# modular_pcb2.net
KiCad netlist of a schematic drawn in EAGLE
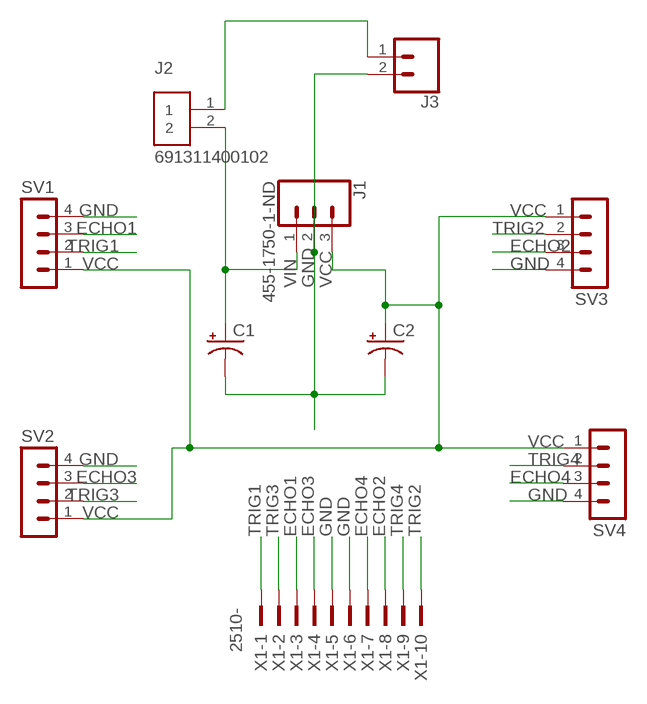
[diagram p0: schematic, sheet 1]

(export (version "E")
  (design (tool "Eeschema 10.0.6"))
  (components
    (comp (ref "C1")
      (value "1F-2.7V(PTH)CPOL-RADIAL-1H-2.7V")
      (footprint "eagle-import:CPOL-RADIAL-1F-2.7V")
      (libsource (lib "eagle-import") (part "1F-2.7V(PTH)CPOL-RADIAL-1H-2.7V"))
    )
    (comp (ref "C2")
      (value "1F-2.7V(PTH)CPOL-RADIAL-1H-2.7V")
      (footprint "eagle-import:CPOL-RADIAL-1F-2.7V")
      (libsource (lib "eagle-import") (part "1F-2.7V(PTH)CPOL-RADIAL-1H-2.7V"))
    )
    (comp (ref "J1")
      (value "455-1750-1-ND")
      (footprint "eagle-import:1X03")
      (libsource (lib "eagle-import") (part "CONN_03"))
    )
    (comp (ref "J2")
      (value "691311400102")
      (footprint "eagle-import:TERMINALBLOCK_PLUGGABLE-2-7.62MM")
      (fields
        (field (name "DIGIKEY_PART_NO") "732-2823-ND")
        (field (name "MANUFACTURER") "WURTH ELEKTRONIK")
        (field (name "CREATED_BY") "PCBLayout.com")
      )
      (libsource (lib "eagle-import") (part "691311400102"))
    )
    (comp (ref "J3")
      (value "CONN_02")
      (footprint "eagle-import:1X02")
      (libsource (lib "eagle-import") (part "CONN_02"))
    )
    (comp (ref "SV1")
      (value "MA04-1")
      (footprint "eagle-import:MA04-1")
      (libsource (lib "eagle-import") (part "MA04-1"))
    )
    (comp (ref "SV2")
      (value "MA04-1")
      (footprint "eagle-import:MA04-1")
      (libsource (lib "eagle-import") (part "MA04-1"))
    )
    (comp (ref "SV3")
      (value "MA04-1")
      (footprint "eagle-import:MA04-1")
      (libsource (lib "eagle-import") (part "MA04-1"))
    )
    (comp (ref "SV4")
      (value "MA04-1")
      (footprint "eagle-import:MA04-1")
      (libsource (lib "eagle-import") (part "MA04-1"))
    )
    (comp (ref "X1")
      (value "2510-")
      (footprint "eagle-import:PAK100_2500-10")
      (fields (field (name "MF") "3M") (field (name "MPN") "2510-6002UB"))
      (libsource (lib "eagle-import") (part "2510-"))
    )
  )
  (nets
    (net (code "1") (name "/ECHO1") (class "Default")
      (node (ref "SV1") (pin "3") (pinfunction "3_3") (pintype "passive"))
      (node (ref "X1") (pin "3") (pinfunction "KL_3") (pintype "passive"))
    )
    (net (code "2") (name "/ECHO2") (class "Default")
      (node (ref "SV3") (pin "3") (pinfunction "3_3") (pintype "passive"))
      (node (ref "X1") (pin "8") (pinfunction "KL_8") (pintype "passive"))
    )
    (net (code "3") (name "/ECHO3") (class "Default")
      (node (ref "SV2") (pin "3") (pinfunction "3_3") (pintype "passive"))
      (node (ref "X1") (pin "4") (pinfunction "KL_4") (pintype "passive"))
    )
    (net (code "4") (name "/ECHO4") (class "Default")
      (node (ref "SV4") (pin "3") (pinfunction "3_3") (pintype "passive"))
      (node (ref "X1") (pin "7") (pinfunction "KL_7") (pintype "passive"))
    )
    (net (code "5") (name "/GND") (class "Default")
      (node (ref "C1") (pin "-") (pinfunction "-_-") (pintype "passive"))
      (node (ref "C2") (pin "-") (pinfunction "-_-") (pintype "passive"))
      (node (ref "J1") (pin "2") (pinfunction "2_2") (pintype "passive"))
      (node (ref "J3") (pin "2") (pinfunction "2_2") (pintype "passive"))
      (node (ref "SV1") (pin "4") (pinfunction "4_4") (pintype "passive"))
      (node (ref "SV2") (pin "4") (pinfunction "4_4") (pintype "passive"))
      (node (ref "SV3") (pin "4") (pinfunction "4_4") (pintype "passive"))
      (node (ref "SV4") (pin "4") (pinfunction "4_4") (pintype "passive"))
      (node (ref "X1") (pin "5") (pinfunction "KL_5") (pintype "passive"))
      (node (ref "X1") (pin "6") (pinfunction "KL_6") (pintype "passive"))
    )
    (net (code "6") (name "/TRIG1") (class "Default")
      (node (ref "SV1") (pin "2") (pinfunction "2_2") (pintype "passive"))
      (node (ref "X1") (pin "1") (pinfunction "KL_1") (pintype "passive"))
    )
    (net (code "7") (name "/TRIG2") (class "Default")
      (node (ref "SV3") (pin "2") (pinfunction "2_2") (pintype "passive"))
      (node (ref "X1") (pin "10") (pinfunction "KL_10") (pintype "passive"))
    )
    (net (code "8") (name "/TRIG3") (class "Default")
      (node (ref "SV2") (pin "2") (pinfunction "2_2") (pintype "passive"))
      (node (ref "X1") (pin "2") (pinfunction "KL_2") (pintype "passive"))
    )
    (net (code "9") (name "/TRIG4") (class "Default")
      (node (ref "SV4") (pin "2") (pinfunction "2_2") (pintype "passive"))
      (node (ref "X1") (pin "9") (pinfunction "KL_9") (pintype "passive"))
    )
    (net (code "10") (name "/VCC") (class "Default")
      (node (ref "C2") (pin "+") (pinfunction "+_+") (pintype "passive"))
      (node (ref "J1") (pin "3") (pinfunction "3_3") (pintype "passive"))
      (node (ref "SV1") (pin "1") (pinfunction "1_1") (pintype "passive"))
      (node (ref "SV2") (pin "1") (pinfunction "1_1") (pintype "passive"))
      (node (ref "SV3") (pin "1") (pinfunction "1_1") (pintype "passive"))
      (node (ref "SV4") (pin "1") (pinfunction "1_1") (pintype "passive"))
    )
    (net (code "11") (name "/VIN") (class "Default")
      (node (ref "C1") (pin "+") (pinfunction "+_+") (pintype "passive"))
      (node (ref "J1") (pin "1") (pinfunction "1_1") (pintype "passive"))
      (node (ref "J2") (pin "2") (pinfunction "2_2") (pintype "passive"))
    )
    (net (code "12") (name "Net-(J2-Pad1)") (class "Default")
      (node (ref "J2") (pin "1") (pinfunction "1_1") (pintype "passive"))
      (node (ref "J3") (pin "1") (pinfunction "1_1") (pintype "passive"))
    )
  )
)
